# sheet1.net
KiCad netlist of a schematic drawn in Altium Designer
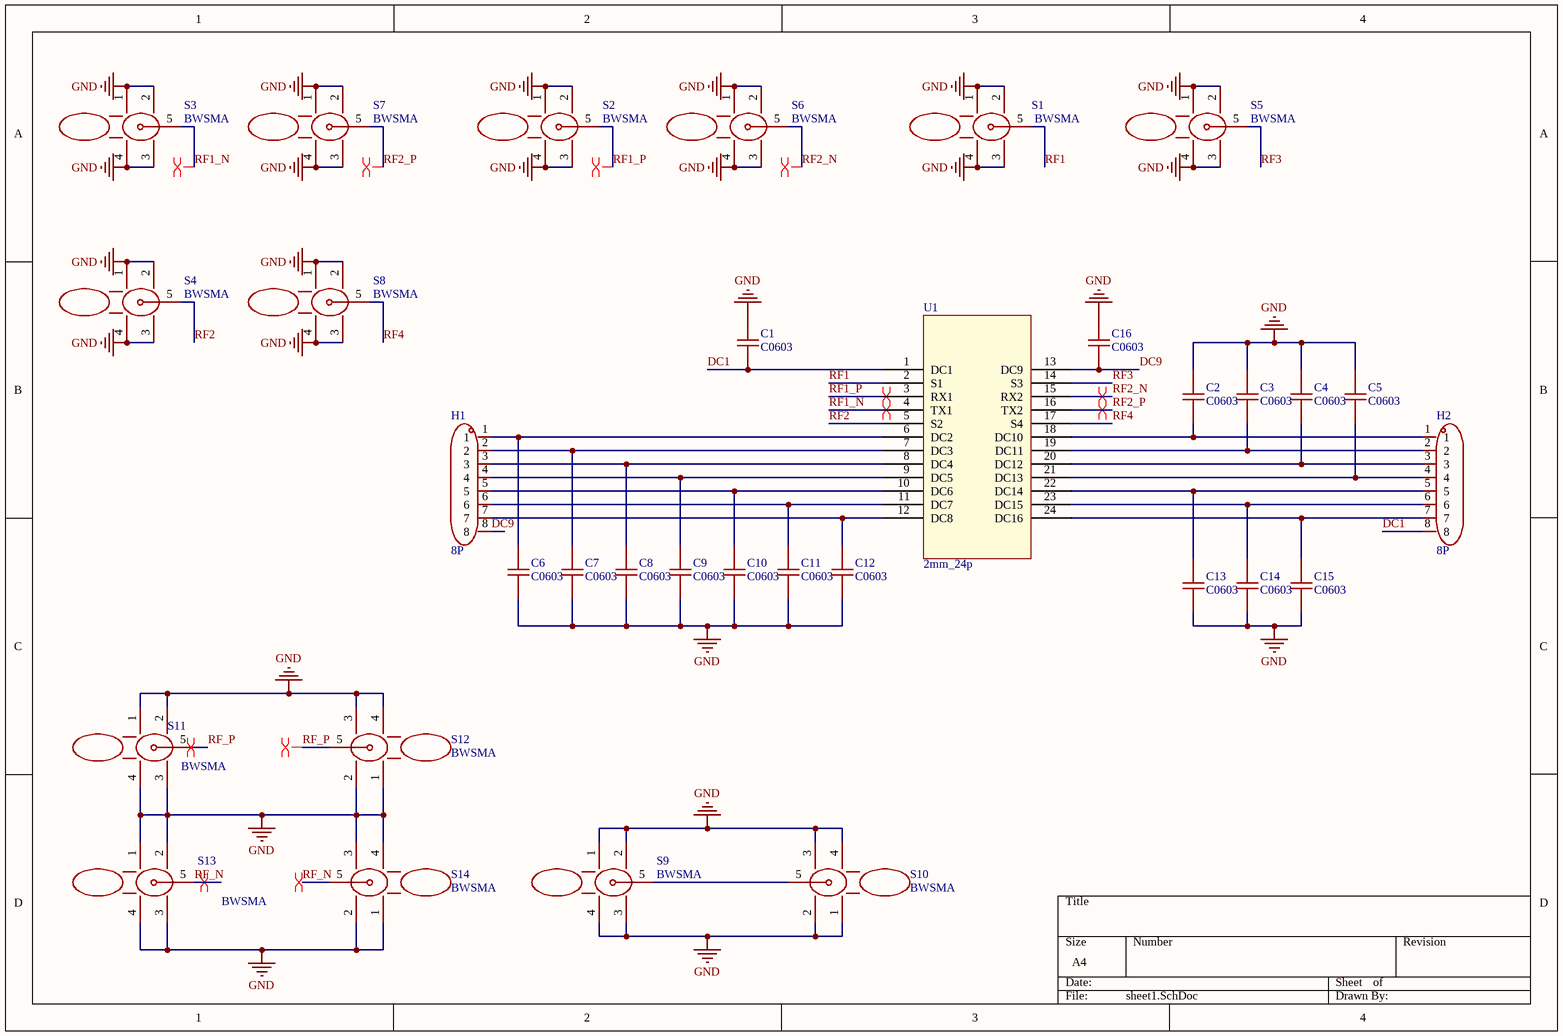
[diagram p0: sheet1.SchDoc]

(export (version "E")
  (design (tool "Eeschema 10.0.6"))
  (components
    (comp (ref "C1") (value "C0603") (footprint "C0603") (libsource (lib "Cap") (part "C0603")))
    (comp (ref "C2") (value "C0603") (footprint "C0603") (libsource (lib "Cap") (part "C0603")))
    (comp (ref "C3") (value "C0603") (footprint "C0603") (libsource (lib "Cap") (part "C0603")))
    (comp (ref "C4") (value "C0603") (footprint "C0603") (libsource (lib "Cap") (part "C0603")))
    (comp (ref "C5") (value "C0603") (footprint "C0603") (libsource (lib "Cap") (part "C0603")))
    (comp (ref "C6") (value "C0603") (footprint "C0603") (libsource (lib "Cap") (part "C0603")))
    (comp (ref "C7") (value "C0603") (footprint "C0603") (libsource (lib "Cap") (part "C0603")))
    (comp (ref "C8") (value "C0603") (footprint "C0603") (libsource (lib "Cap") (part "C0603")))
    (comp (ref "C9") (value "C0603") (footprint "C0603") (libsource (lib "Cap") (part "C0603")))
    (comp (ref "C10") (value "C0603") (footprint "C0603") (libsource (lib "Cap") (part "C0603")))
    (comp (ref "C11") (value "C0603") (footprint "C0603") (libsource (lib "Cap") (part "C0603")))
    (comp (ref "C12") (value "C0603") (footprint "C0603") (libsource (lib "Cap") (part "C0603")))
    (comp (ref "C13") (value "C0603") (footprint "C0603") (libsource (lib "Cap") (part "C0603")))
    (comp (ref "C14") (value "C0603") (footprint "C0603") (libsource (lib "Cap") (part "C0603")))
    (comp (ref "C15") (value "C0603") (footprint "C0603") (libsource (lib "Cap") (part "C0603")))
    (comp (ref "C16") (value "C0603") (footprint "C0603") (libsource (lib "Cap") (part "C0603")))
    (comp (ref "H1") (value "8P") (footprint "8P") (libsource (lib "Header") (part "8P")))
    (comp (ref "H2") (value "8P") (footprint "8P") (libsource (lib "Header") (part "8P")))
    (comp (ref "S1") (value "BWSMA") (footprint "BWSMA") (libsource (lib "SMA") (part "BWSMA")))
    (comp (ref "S2") (value "BWSMA") (footprint "BWSMA") (libsource (lib "SMA") (part "BWSMA")))
    (comp (ref "S3") (value "BWSMA") (footprint "BWSMA") (libsource (lib "SMA") (part "BWSMA")))
    (comp (ref "S4") (value "BWSMA") (footprint "BWSMA") (libsource (lib "SMA") (part "BWSMA")))
    (comp (ref "S5") (value "BWSMA") (footprint "BWSMA") (libsource (lib "SMA") (part "BWSMA")))
    (comp (ref "S6") (value "BWSMA") (footprint "BWSMA") (libsource (lib "SMA") (part "BWSMA")))
    (comp (ref "S7") (value "BWSMA") (footprint "BWSMA") (libsource (lib "SMA") (part "BWSMA")))
    (comp (ref "S8") (value "BWSMA") (footprint "BWSMA") (libsource (lib "SMA") (part "BWSMA")))
    (comp (ref "S9") (value "BWSMA") (footprint "BWSMA") (libsource (lib "SMA") (part "BWSMA")))
    (comp (ref "S10") (value "BWSMA") (footprint "BWSMA") (libsource (lib "SMA") (part "BWSMA")))
    (comp (ref "S11") (value "BWSMA") (footprint "BWSMA") (libsource (lib "SMA") (part "BWSMA")))
    (comp (ref "S12") (value "BWSMA") (footprint "BWSMA") (libsource (lib "SMA") (part "BWSMA")))
    (comp (ref "S13") (value "BWSMA") (footprint "BWSMA") (libsource (lib "SMA") (part "BWSMA")))
    (comp (ref "S14") (value "BWSMA") (footprint "BWSMA") (libsource (lib "SMA") (part "BWSMA")))
    (comp (ref "U1") (value "2mm_24p") (footprint "2MM_8AC_16DC") (libsource (lib "Chips") (part "2mm_24p")))
  )
  (nets
    (net (code "1") (name "/DC1") (class "Default")
      (node (ref "C1") (pin "1") (pinfunction "1_1") (pintype "passive"))
      (node (ref "H2") (pin "8") (pinfunction "8_8") (pintype "passive"))
      (node (ref "U1") (pin "1") (pinfunction "DC1_1") (pintype "passive"))
    )
    (net (code "2") (name "/DC9") (class "Default")
      (node (ref "C16") (pin "1") (pinfunction "1_1") (pintype "passive"))
      (node (ref "H1") (pin "8") (pinfunction "8_8") (pintype "passive"))
      (node (ref "U1") (pin "13") (pinfunction "DC9_13") (pintype "passive"))
    )
    (net (code "3") (name "/RF1") (class "Default")
      (node (ref "S1") (pin "5") (pinfunction "5_5") (pintype "passive"))
      (node (ref "U1") (pin "2") (pinfunction "S1_2") (pintype "passive"))
    )
    (net (code "4") (name "/RF1_N") (class "Default")
      (node (ref "S3") (pin "5") (pinfunction "5_5") (pintype "passive"))
      (node (ref "U1") (pin "4") (pinfunction "TX1_4") (pintype "passive"))
    )
    (net (code "5") (name "/RF1_P") (class "Default")
      (node (ref "S2") (pin "5") (pinfunction "5_5") (pintype "passive"))
      (node (ref "U1") (pin "3") (pinfunction "RX1_3") (pintype "passive"))
    )
    (net (code "6") (name "/RF2") (class "Default")
      (node (ref "S4") (pin "5") (pinfunction "5_5") (pintype "passive"))
      (node (ref "U1") (pin "5") (pinfunction "S2_5") (pintype "passive"))
    )
    (net (code "7") (name "/RF2_N") (class "Default")
      (node (ref "S6") (pin "5") (pinfunction "5_5") (pintype "passive"))
      (node (ref "U1") (pin "15") (pinfunction "RX2_15") (pintype "passive"))
    )
    (net (code "8") (name "/RF2_P") (class "Default")
      (node (ref "S7") (pin "5") (pinfunction "5_5") (pintype "passive"))
      (node (ref "U1") (pin "16") (pinfunction "TX2_16") (pintype "passive"))
    )
    (net (code "9") (name "/RF3") (class "Default")
      (node (ref "S5") (pin "5") (pinfunction "5_5") (pintype "passive"))
      (node (ref "U1") (pin "14") (pinfunction "S3_14") (pintype "passive"))
    )
    (net (code "10") (name "/RF4") (class "Default")
      (node (ref "S8") (pin "5") (pinfunction "5_5") (pintype "passive"))
      (node (ref "U1") (pin "17") (pinfunction "S4_17") (pintype "passive"))
    )
    (net (code "11") (name "/RF_N") (class "Default")
      (node (ref "S13") (pin "5") (pinfunction "5_5") (pintype "passive"))
      (node (ref "S14") (pin "5") (pinfunction "5_5") (pintype "passive"))
    )
    (net (code "12") (name "/RF_P") (class "Default")
      (node (ref "S11") (pin "5") (pinfunction "5_5") (pintype "passive"))
      (node (ref "S12") (pin "5") (pinfunction "5_5") (pintype "passive"))
    )
    (net (code "13") (name "GND") (class "Default")
      (node (ref "C1") (pin "2") (pinfunction "2_2") (pintype "passive"))
      (node (ref "C10") (pin "1") (pinfunction "1_1") (pintype "passive"))
      (node (ref "C11") (pin "1") (pinfunction "1_1") (pintype "passive"))
      (node (ref "C12") (pin "1") (pinfunction "1_1") (pintype "passive"))
      (node (ref "C13") (pin "1") (pinfunction "1_1") (pintype "passive"))
      (node (ref "C14") (pin "1") (pinfunction "1_1") (pintype "passive"))
      (node (ref "C15") (pin "1") (pinfunction "1_1") (pintype "passive"))
      (node (ref "C16") (pin "2") (pinfunction "2_2") (pintype "passive"))
      (node (ref "C2") (pin "2") (pinfunction "2_2") (pintype "passive"))
      (node (ref "C3") (pin "2") (pinfunction "2_2") (pintype "passive"))
      (node (ref "C4") (pin "2") (pinfunction "2_2") (pintype "passive"))
      (node (ref "C5") (pin "2") (pinfunction "2_2") (pintype "passive"))
      (node (ref "C6") (pin "1") (pinfunction "1_1") (pintype "passive"))
      (node (ref "C7") (pin "1") (pinfunction "1_1") (pintype "passive"))
      (node (ref "C8") (pin "1") (pinfunction "1_1") (pintype "passive"))
      (node (ref "C9") (pin "1") (pinfunction "1_1") (pintype "passive"))
      (node (ref "S1") (pin "1") (pinfunction "1_1") (pintype "passive"))
      (node (ref "S1") (pin "2") (pinfunction "2_2") (pintype "passive"))
      (node (ref "S1") (pin "3") (pinfunction "3_3") (pintype "passive"))
      (node (ref "S1") (pin "4") (pinfunction "4_4") (pintype "passive"))
      (node (ref "S10") (pin "1") (pinfunction "1_1") (pintype "passive"))
      (node (ref "S10") (pin "2") (pinfunction "2_2") (pintype "passive"))
      (node (ref "S10") (pin "3") (pinfunction "3_3") (pintype "passive"))
      (node (ref "S10") (pin "4") (pinfunction "4_4") (pintype "passive"))
      (node (ref "S11") (pin "1") (pinfunction "1_1") (pintype "passive"))
      (node (ref "S11") (pin "2") (pinfunction "2_2") (pintype "passive"))
      (node (ref "S11") (pin "3") (pinfunction "3_3") (pintype "passive"))
      (node (ref "S11") (pin "4") (pinfunction "4_4") (pintype "passive"))
      (node (ref "S12") (pin "1") (pinfunction "1_1") (pintype "passive"))
      (node (ref "S12") (pin "2") (pinfunction "2_2") (pintype "passive"))
      (node (ref "S12") (pin "3") (pinfunction "3_3") (pintype "passive"))
      (node (ref "S12") (pin "4") (pinfunction "4_4") (pintype "passive"))
      (node (ref "S13") (pin "1") (pinfunction "1_1") (pintype "passive"))
      (node (ref "S13") (pin "2") (pinfunction "2_2") (pintype "passive"))
      (node (ref "S13") (pin "3") (pinfunction "3_3") (pintype "passive"))
      (node (ref "S13") (pin "4") (pinfunction "4_4") (pintype "passive"))
      (node (ref "S14") (pin "1") (pinfunction "1_1") (pintype "passive"))
      (node (ref "S14") (pin "2") (pinfunction "2_2") (pintype "passive"))
      (node (ref "S14") (pin "3") (pinfunction "3_3") (pintype "passive"))
      (node (ref "S14") (pin "4") (pinfunction "4_4") (pintype "passive"))
      (node (ref "S2") (pin "1") (pinfunction "1_1") (pintype "passive"))
      (node (ref "S2") (pin "2") (pinfunction "2_2") (pintype "passive"))
      (node (ref "S2") (pin "3") (pinfunction "3_3") (pintype "passive"))
      (node (ref "S2") (pin "4") (pinfunction "4_4") (pintype "passive"))
      (node (ref "S3") (pin "1") (pinfunction "1_1") (pintype "passive"))
      (node (ref "S3") (pin "2") (pinfunction "2_2") (pintype "passive"))
      (node (ref "S3") (pin "3") (pinfunction "3_3") (pintype "passive"))
      (node (ref "S3") (pin "4") (pinfunction "4_4") (pintype "passive"))
      (node (ref "S4") (pin "1") (pinfunction "1_1") (pintype "passive"))
      (node (ref "S4") (pin "2") (pinfunction "2_2") (pintype "passive"))
      (node (ref "S4") (pin "3") (pinfunction "3_3") (pintype "passive"))
      (node (ref "S4") (pin "4") (pinfunction "4_4") (pintype "passive"))
      (node (ref "S5") (pin "1") (pinfunction "1_1") (pintype "passive"))
      (node (ref "S5") (pin "2") (pinfunction "2_2") (pintype "passive"))
      (node (ref "S5") (pin "3") (pinfunction "3_3") (pintype "passive"))
      (node (ref "S5") (pin "4") (pinfunction "4_4") (pintype "passive"))
      (node (ref "S6") (pin "1") (pinfunction "1_1") (pintype "passive"))
      (node (ref "S6") (pin "2") (pinfunction "2_2") (pintype "passive"))
      (node (ref "S6") (pin "3") (pinfunction "3_3") (pintype "passive"))
      (node (ref "S6") (pin "4") (pinfunction "4_4") (pintype "passive"))
      (node (ref "S7") (pin "1") (pinfunction "1_1") (pintype "passive"))
      (node (ref "S7") (pin "2") (pinfunction "2_2") (pintype "passive"))
      (node (ref "S7") (pin "3") (pinfunction "3_3") (pintype "passive"))
      (node (ref "S7") (pin "4") (pinfunction "4_4") (pintype "passive"))
      (node (ref "S8") (pin "1") (pinfunction "1_1") (pintype "passive"))
      (node (ref "S8") (pin "2") (pinfunction "2_2") (pintype "passive"))
      (node (ref "S8") (pin "3") (pinfunction "3_3") (pintype "passive"))
      (node (ref "S8") (pin "4") (pinfunction "4_4") (pintype "passive"))
      (node (ref "S9") (pin "1") (pinfunction "1_1") (pintype "passive"))
      (node (ref "S9") (pin "2") (pinfunction "2_2") (pintype "passive"))
      (node (ref "S9") (pin "3") (pinfunction "3_3") (pintype "passive"))
      (node (ref "S9") (pin "4") (pinfunction "4_4") (pintype "passive"))
    )
    (net (code "14") (name "Net-(S10-Pad5)") (class "Default")
      (node (ref "S10") (pin "5") (pinfunction "5_5") (pintype "passive"))
      (node (ref "S9") (pin "5") (pinfunction "5_5") (pintype "passive"))
    )
    (net (code "15") (name "Net-(U1-DC2)") (class "Default")
      (node (ref "C6") (pin "2") (pinfunction "2_2") (pintype "passive"))
      (node (ref "H1") (pin "1") (pinfunction "1_1") (pintype "passive"))
      (node (ref "U1") (pin "6") (pinfunction "DC2_6") (pintype "passive"))
    )
    (net (code "16") (name "Net-(U1-DC3)") (class "Default")
      (node (ref "C7") (pin "2") (pinfunction "2_2") (pintype "passive"))
      (node (ref "H1") (pin "2") (pinfunction "2_2") (pintype "passive"))
      (node (ref "U1") (pin "7") (pinfunction "DC3_7") (pintype "passive"))
    )
    (net (code "17") (name "Net-(U1-DC4)") (class "Default")
      (node (ref "C8") (pin "2") (pinfunction "2_2") (pintype "passive"))
      (node (ref "H1") (pin "3") (pinfunction "3_3") (pintype "passive"))
      (node (ref "U1") (pin "8") (pinfunction "DC4_8") (pintype "passive"))
    )
    (net (code "18") (name "Net-(U1-DC5)") (class "Default")
      (node (ref "C9") (pin "2") (pinfunction "2_2") (pintype "passive"))
      (node (ref "H1") (pin "4") (pinfunction "4_4") (pintype "passive"))
      (node (ref "U1") (pin "9") (pinfunction "DC5_9") (pintype "passive"))
    )
    (net (code "19") (name "Net-(U1-DC6)") (class "Default")
      (node (ref "C10") (pin "2") (pinfunction "2_2") (pintype "passive"))
      (node (ref "H1") (pin "5") (pinfunction "5_5") (pintype "passive"))
      (node (ref "U1") (pin "10") (pinfunction "DC6_10") (pintype "passive"))
    )
    (net (code "20") (name "Net-(U1-DC7)") (class "Default")
      (node (ref "C11") (pin "2") (pinfunction "2_2") (pintype "passive"))
      (node (ref "H1") (pin "6") (pinfunction "6_6") (pintype "passive"))
      (node (ref "U1") (pin "11") (pinfunction "DC7_11") (pintype "passive"))
    )
    (net (code "21") (name "Net-(U1-DC8)") (class "Default")
      (node (ref "C12") (pin "2") (pinfunction "2_2") (pintype "passive"))
      (node (ref "H1") (pin "7") (pinfunction "7_7") (pintype "passive"))
      (node (ref "U1") (pin "12") (pinfunction "DC8_12") (pintype "passive"))
    )
    (net (code "22") (name "Net-(U1-DC10)") (class "Default")
      (node (ref "C2") (pin "1") (pinfunction "1_1") (pintype "passive"))
      (node (ref "H2") (pin "1") (pinfunction "1_1") (pintype "passive"))
      (node (ref "U1") (pin "18") (pinfunction "DC10_18") (pintype "passive"))
    )
    (net (code "23") (name "Net-(U1-DC11)") (class "Default")
      (node (ref "C3") (pin "1") (pinfunction "1_1") (pintype "passive"))
      (node (ref "H2") (pin "2") (pinfunction "2_2") (pintype "passive"))
      (node (ref "U1") (pin "19") (pinfunction "DC11_19") (pintype "passive"))
    )
    (net (code "24") (name "Net-(U1-DC12)") (class "Default")
      (node (ref "C4") (pin "1") (pinfunction "1_1") (pintype "passive"))
      (node (ref "H2") (pin "3") (pinfunction "3_3") (pintype "passive"))
      (node (ref "U1") (pin "20") (pinfunction "DC12_20") (pintype "passive"))
    )
    (net (code "25") (name "Net-(U1-DC13)") (class "Default")
      (node (ref "C5") (pin "1") (pinfunction "1_1") (pintype "passive"))
      (node (ref "H2") (pin "4") (pinfunction "4_4") (pintype "passive"))
      (node (ref "U1") (pin "21") (pinfunction "DC13_21") (pintype "passive"))
    )
    (net (code "26") (name "Net-(U1-DC14)") (class "Default")
      (node (ref "C13") (pin "2") (pinfunction "2_2") (pintype "passive"))
      (node (ref "H2") (pin "5") (pinfunction "5_5") (pintype "passive"))
      (node (ref "U1") (pin "22") (pinfunction "DC14_22") (pintype "passive"))
    )
    (net (code "27") (name "Net-(U1-DC15)") (class "Default")
      (node (ref "C14") (pin "2") (pinfunction "2_2") (pintype "passive"))
      (node (ref "H2") (pin "6") (pinfunction "6_6") (pintype "passive"))
      (node (ref "U1") (pin "23") (pinfunction "DC15_23") (pintype "passive"))
    )
    (net (code "28") (name "Net-(U1-DC16)") (class "Default")
      (node (ref "C15") (pin "2") (pinfunction "2_2") (pintype "passive"))
      (node (ref "H2") (pin "7") (pinfunction "7_7") (pintype "passive"))
      (node (ref "U1") (pin "24") (pinfunction "DC16_24") (pintype "passive"))
    )
  )
)
